# powerbrick_v1.net
KiCad netlist of a schematic drawn in EAGLE
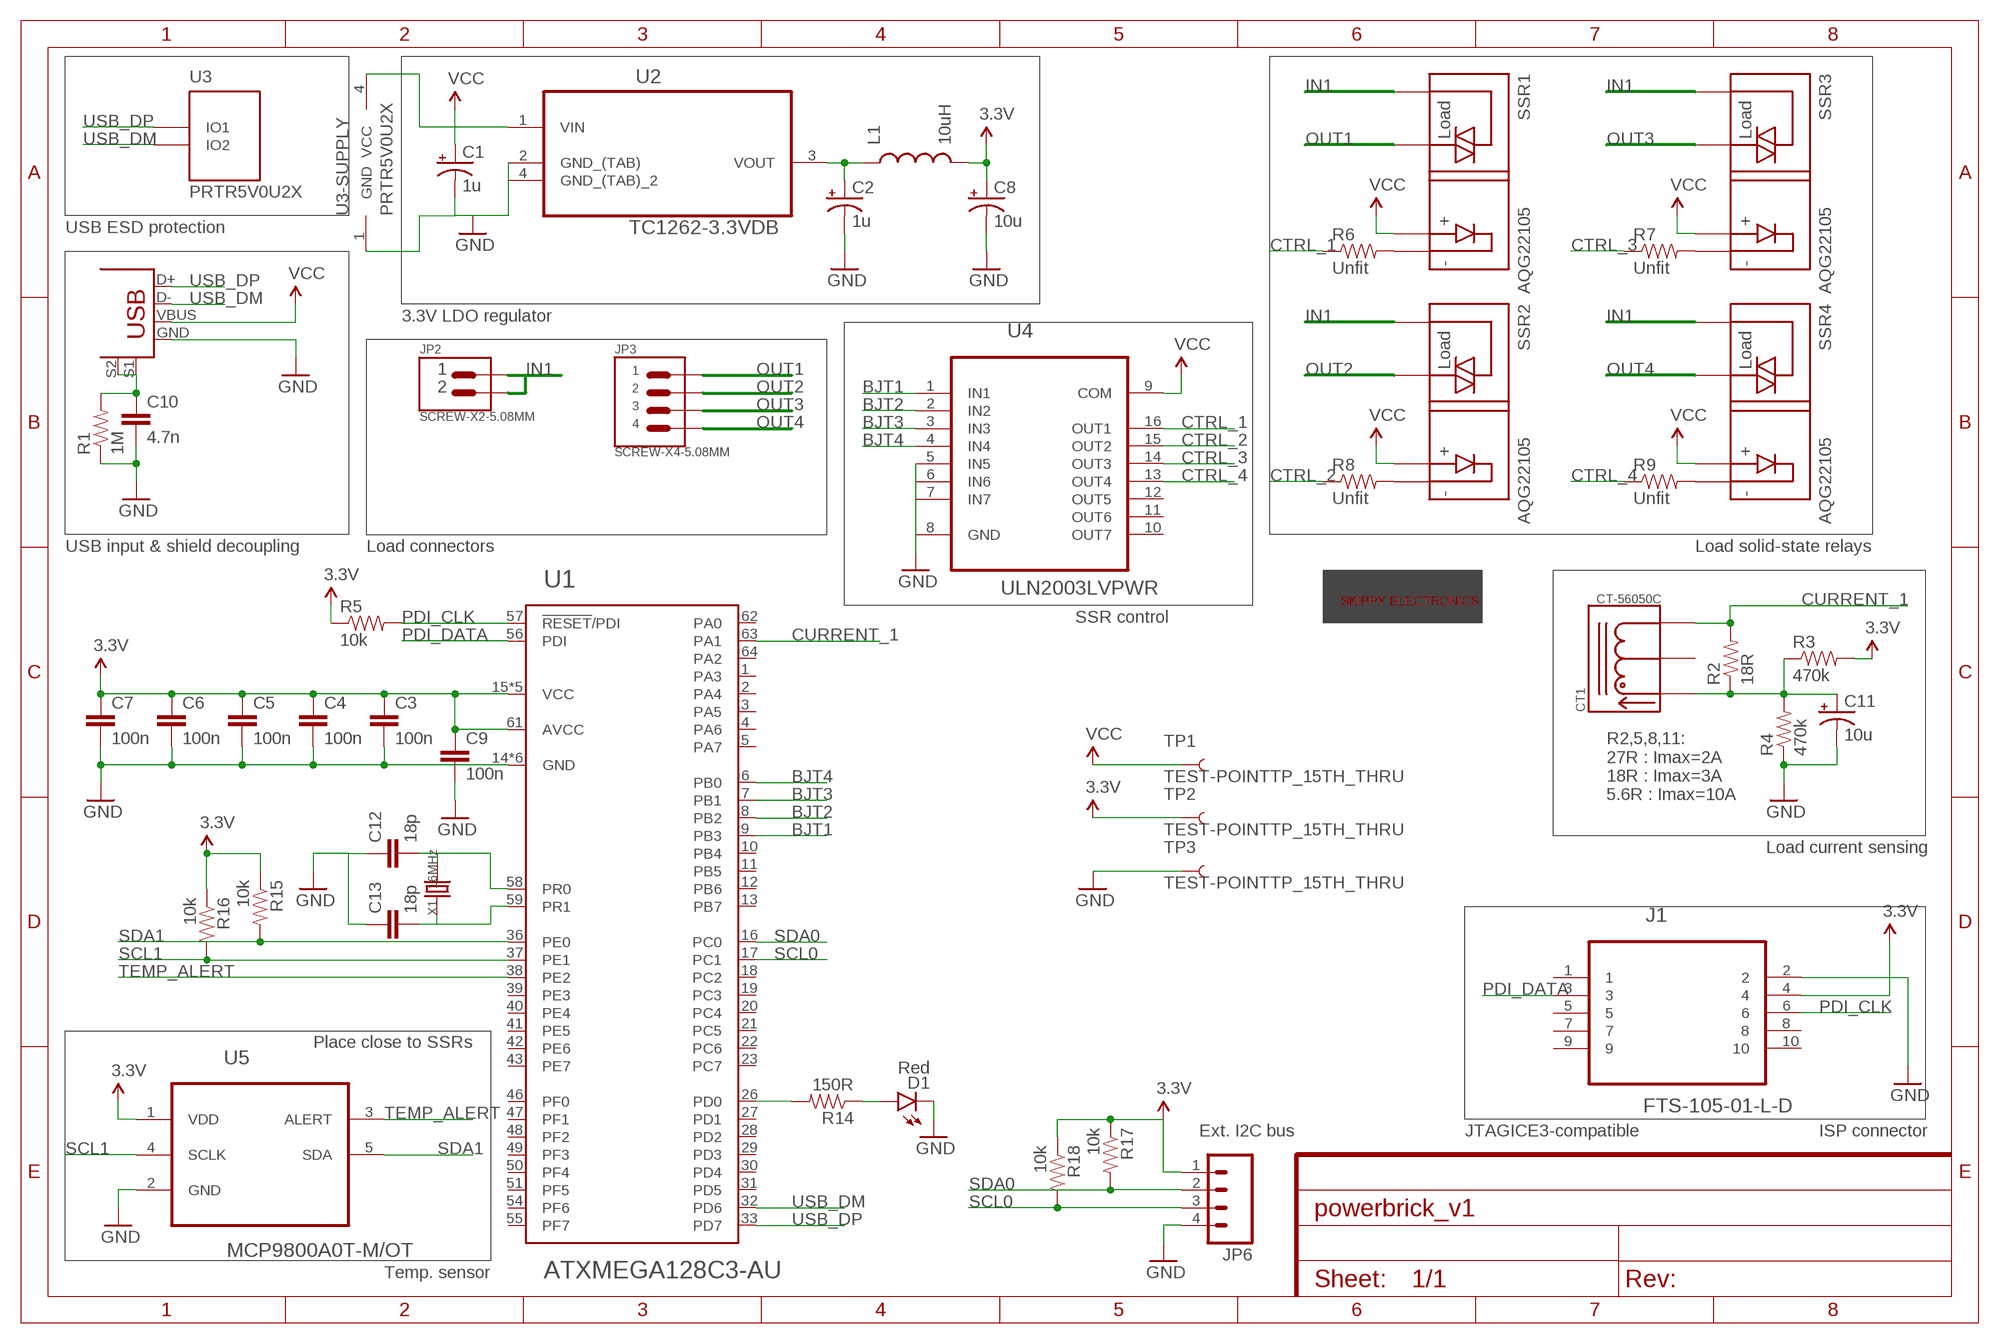
[diagram p0: schematic, sheet 1]

(export (version "E")
  (design (tool "Eeschema 10.0.6"))
  (components
    (comp (ref "C1")
      (value "1u")
      (footprint "eagle-import:EIA3216-KIT")
      (libsource (lib "eagle-import") (part "CAP_POL1206-KIT"))
    )
    (comp (ref "C2")
      (value "1u")
      (footprint "eagle-import:EIA3216-KIT")
      (libsource (lib "eagle-import") (part "CAP_POL1206-KIT"))
    )
    (comp (ref "C3")
      (value "100n")
      (footprint "eagle-import:0805")
      (libsource (lib "eagle-import") (part "CAP0805"))
    )
    (comp (ref "C4")
      (value "100n")
      (footprint "eagle-import:0805")
      (libsource (lib "eagle-import") (part "CAP0805"))
    )
    (comp (ref "C5")
      (value "100n")
      (footprint "eagle-import:0805")
      (libsource (lib "eagle-import") (part "CAP0805"))
    )
    (comp (ref "C6")
      (value "100n")
      (footprint "eagle-import:0805")
      (libsource (lib "eagle-import") (part "CAP0805"))
    )
    (comp (ref "C7")
      (value "100n")
      (footprint "eagle-import:0805")
      (libsource (lib "eagle-import") (part "CAP0805"))
    )
    (comp (ref "C8")
      (value "10u")
      (footprint "eagle-import:EIA3216-KIT")
      (libsource (lib "eagle-import") (part "CAP_POL1206-KIT"))
    )
    (comp (ref "C9")
      (value "100n")
      (footprint "eagle-import:0805")
      (libsource (lib "eagle-import") (part "CAP0805"))
    )
    (comp (ref "C10")
      (value "4.7n")
      (footprint "eagle-import:0805")
      (libsource (lib "eagle-import") (part "CAP0805"))
    )
    (comp (ref "C11")
      (value "10u")
      (footprint "eagle-import:EIA3216-KIT")
      (libsource (lib "eagle-import") (part "CAP_POL1206-KIT"))
    )
    (comp (ref "C12")
      (value "18p")
      (footprint "eagle-import:0805")
      (libsource (lib "eagle-import") (part "CAP0805"))
    )
    (comp (ref "C13")
      (value "18p")
      (footprint "eagle-import:0805")
      (libsource (lib "eagle-import") (part "CAP0805"))
    )
    (comp (ref "CT1")
      (value "CT-56050C")
      (footprint "eagle-import:CT-56050C")
      (libsource (lib "eagle-import") (part "CT-56050C"))
    )
    (comp (ref "D1")
      (value "Red")
      (footprint "eagle-import:LED5MM")
      (libsource (lib "eagle-import") (part "LED5MM"))
    )
    (comp (ref "J1")
      (value "FTS-105-01-L-D")
      (footprint "eagle-import:SAMTEC_FTS-105-01-L-D")
      (libsource (lib "eagle-import") (part "FTS-105-01-L-D"))
    )
    (comp (ref "JP1")
      (value "USB+SHIELD")
      (footprint "eagle-import:USB-B-PTH")
      (libsource (lib "eagle-import") (part "USB+SHIELD"))
    )
    (comp (ref "JP2")
      (value "SCREW-X2-5.08MM")
      (footprint "eagle-import:1X02-5.08MM")
      (libsource (lib "eagle-import") (part "SCREW-X2-5.08MM"))
    )
    (comp (ref "JP3")
      (value "SCREW-X4-5.08MM")
      (footprint "eagle-import:1X04")
      (libsource (lib "eagle-import") (part "SCREW-X4-5.08MM"))
    )
    (comp (ref "JP6")
      (value "M04POLAR_LOCK")
      (footprint "eagle-import:MOLEX-1X4_LOCK")
      (libsource (lib "eagle-import") (part "M04POLAR_LOCK"))
    )
    (comp (ref "L1")
      (value "10uH")
      (footprint "eagle-import:SRN6045")
      (libsource (lib "eagle-import") (part "INDUCTORBOURNS_SRN6045"))
    )
    (comp (ref "R1")
      (value "1M")
      (footprint "eagle-import:0805")
      (libsource (lib "eagle-import") (part "RESISTOR0805-RES"))
    )
    (comp (ref "R2")
      (value "18R")
      (footprint "eagle-import:R2512")
      (libsource (lib "eagle-import") (part "RESISTOR2512"))
    )
    (comp (ref "R3")
      (value "470k")
      (footprint "eagle-import:0805")
      (libsource (lib "eagle-import") (part "RESISTOR0805-RES"))
    )
    (comp (ref "R4")
      (value "470k")
      (footprint "eagle-import:0805")
      (libsource (lib "eagle-import") (part "RESISTOR0805-RES"))
    )
    (comp (ref "R5")
      (value "10k")
      (footprint "eagle-import:0805")
      (libsource (lib "eagle-import") (part "RESISTOR0805-RES"))
    )
    (comp (ref "R6")
      (value "Unfit")
      (footprint "eagle-import:0805")
      (libsource (lib "eagle-import") (part "RESISTOR0805-RES"))
    )
    (comp (ref "R7")
      (value "Unfit")
      (footprint "eagle-import:0805")
      (libsource (lib "eagle-import") (part "RESISTOR0805-RES"))
    )
    (comp (ref "R8")
      (value "Unfit")
      (footprint "eagle-import:0805")
      (libsource (lib "eagle-import") (part "RESISTOR0805-RES"))
    )
    (comp (ref "R9")
      (value "Unfit")
      (footprint "eagle-import:0805")
      (libsource (lib "eagle-import") (part "RESISTOR0805-RES"))
    )
    (comp (ref "R14")
      (value "150R")
      (footprint "eagle-import:0805")
      (libsource (lib "eagle-import") (part "RESISTOR0805-RES"))
    )
    (comp (ref "R15")
      (value "10k")
      (footprint "eagle-import:0805")
      (libsource (lib "eagle-import") (part "RESISTOR0805-RES"))
    )
    (comp (ref "R16")
      (value "10k")
      (footprint "eagle-import:0805")
      (libsource (lib "eagle-import") (part "RESISTOR0805-RES"))
    )
    (comp (ref "R17")
      (value "10k")
      (footprint "eagle-import:0805")
      (libsource (lib "eagle-import") (part "RESISTOR0805-RES"))
    )
    (comp (ref "R18")
      (value "10k")
      (footprint "eagle-import:0805")
      (libsource (lib "eagle-import") (part "RESISTOR0805-RES"))
    )
    (comp (ref "SSR1")
      (value "AQG22105")
      (footprint "eagle-import:SSR-100-400-300")
      (libsource (lib "eagle-import") (part "AQG22105"))
    )
    (comp (ref "SSR2")
      (value "AQG22105")
      (footprint "eagle-import:SSR-100-400-300")
      (libsource (lib "eagle-import") (part "AQG22105"))
    )
    (comp (ref "SSR3")
      (value "AQG22105")
      (footprint "eagle-import:SSR-100-400-300")
      (libsource (lib "eagle-import") (part "AQG22105"))
    )
    (comp (ref "SSR4")
      (value "AQG22105")
      (footprint "eagle-import:SSR-100-400-300")
      (libsource (lib "eagle-import") (part "AQG22105"))
    )
    (comp (ref "TP1")
      (value "TEST-POINTTP_15TH_THRU")
      (footprint "eagle-import:TP_15TH")
      (libsource (lib "eagle-import") (part "TEST-POINTTP_15TH_THRU"))
    )
    (comp (ref "TP2")
      (value "TEST-POINTTP_15TH_THRU")
      (footprint "eagle-import:TP_15TH")
      (libsource (lib "eagle-import") (part "TEST-POINTTP_15TH_THRU"))
    )
    (comp (ref "TP3")
      (value "TEST-POINTTP_15TH_THRU")
      (footprint "eagle-import:TP_15TH")
      (libsource (lib "eagle-import") (part "TEST-POINTTP_15TH_THRU"))
    )
    (comp (ref "U$2")
      (value "SKIPPYTXT-PLC-10MM")
      (footprint "eagle-import:SKIPPYTXT-PLC-10MM")
      (libsource (lib "eagle-import") (part "SKIPPYTXT-PLC-10MM"))
    )
    (comp (ref "U1")
      (value "ATXMEGA128C3-AU")
      (footprint "eagle-import:TQFP-64A-64")
      (libsource (lib "eagle-import") (part "ATXMEGA128C3-AU"))
    )
    (comp (ref "U2")
      (value "TC1262-3.3VDB")
      (footprint "eagle-import:SOT230P700X180-4N")
      (libsource (lib "eagle-import") (part "TC1262-3.3VDB"))
    )
    (comp (ref "U3")
      (value "PRTR5V0U2X")
      (footprint "eagle-import:SOT-143B")
      (libsource (lib "eagle-import") (part "PRTR5V0U2X?"))
    )
    (comp (ref "U4")
      (value "ULN2003LVPWR")
      (footprint "eagle-import:SOP65P640X120-16N")
      (libsource (lib "eagle-import") (part "ULN2003LVPWR"))
    )
    (comp (ref "U5")
      (value "MCP9800A0T-M/OT")
      (footprint "eagle-import:SOT95P280X145-5N")
      (libsource (lib "eagle-import") (part "MCP9800A0T-M/OT"))
    )
    (comp (ref "X1")
      (value "16MHz")
      (footprint "eagle-import:HC49S")
      (libsource (lib "eagle-import") (part "CRYSTAL'HC49S'"))
    )
  )
  (nets
    (net (code "1") (name "/BJT1") (class "Default")
      (node (ref "U1") (pin "9") (pinfunction "PB3_9") (pintype "bidirectional"))
      (node (ref "U4") (pin "1") (pinfunction "IN1_1") (pintype "input"))
    )
    (net (code "2") (name "/BJT2") (class "Default")
      (node (ref "U1") (pin "8") (pinfunction "PB2_8") (pintype "bidirectional"))
      (node (ref "U4") (pin "2") (pinfunction "IN2_2") (pintype "input"))
    )
    (net (code "3") (name "/BJT3") (class "Default")
      (node (ref "U1") (pin "7") (pinfunction "PB1_7") (pintype "bidirectional"))
      (node (ref "U4") (pin "3") (pinfunction "IN3_3") (pintype "input"))
    )
    (net (code "4") (name "/BJT4") (class "Default")
      (node (ref "U1") (pin "6") (pinfunction "PB0_6") (pintype "bidirectional"))
      (node (ref "U4") (pin "4") (pinfunction "IN4_4") (pintype "input"))
    )
    (net (code "5") (name "/CTRL_1") (class "Default")
      (node (ref "R6") (pin "1") (pinfunction "1_1") (pintype "passive"))
      (node (ref "U4") (pin "16") (pinfunction "OUT1_16") (pintype "output"))
    )
    (net (code "6") (name "/CTRL_2") (class "Default")
      (node (ref "R8") (pin "1") (pinfunction "1_1") (pintype "passive"))
      (node (ref "U4") (pin "15") (pinfunction "OUT2_15") (pintype "output"))
    )
    (net (code "7") (name "/CTRL_3") (class "Default")
      (node (ref "R7") (pin "1") (pinfunction "1_1") (pintype "passive"))
      (node (ref "U4") (pin "14") (pinfunction "OUT3_14") (pintype "output"))
    )
    (net (code "8") (name "/CTRL_4") (class "Default")
      (node (ref "R9") (pin "1") (pinfunction "1_1") (pintype "passive"))
      (node (ref "U4") (pin "13") (pinfunction "OUT4_13") (pintype "output"))
    )
    (net (code "9") (name "/CURRENT_1") (class "Default")
      (node (ref "CT1") (pin "P$3") (pinfunction "P$3_P$3") (pintype "bidirectional"))
      (node (ref "R2") (pin "2") (pinfunction "2_2") (pintype "passive"))
      (node (ref "U1") (pin "63") (pinfunction "PA1_63") (pintype "bidirectional"))
    )
    (net (code "10") (name "/IN1") (class "Default")
      (node (ref "JP2") (pin "P$1") (pinfunction "P$1_P$1") (pintype "bidirectional"))
      (node (ref "JP2") (pin "P$2") (pinfunction "P$2_P$2") (pintype "bidirectional"))
      (node (ref "SSR1") (pin "P$4") (pinfunction "P$1_P$4") (pintype "bidirectional"))
      (node (ref "SSR2") (pin "P$4") (pinfunction "P$1_P$4") (pintype "bidirectional"))
      (node (ref "SSR3") (pin "P$4") (pinfunction "P$1_P$4") (pintype "bidirectional"))
      (node (ref "SSR4") (pin "P$4") (pinfunction "P$1_P$4") (pintype "bidirectional"))
    )
    (net (code "11") (name "/OUT1") (class "Default")
      (node (ref "JP3") (pin "P$1") (pinfunction "P$1_P$1") (pintype "bidirectional"))
      (node (ref "SSR1") (pin "P$3") (pinfunction "P$2_P$3") (pintype "bidirectional"))
    )
    (net (code "12") (name "/OUT2") (class "Default")
      (node (ref "JP3") (pin "P$2") (pinfunction "P$2_P$2") (pintype "bidirectional"))
      (node (ref "SSR2") (pin "P$3") (pinfunction "P$2_P$3") (pintype "bidirectional"))
    )
    (net (code "13") (name "/OUT3") (class "Default")
      (node (ref "JP3") (pin "P$3") (pinfunction "P$3_P$3") (pintype "bidirectional"))
      (node (ref "SSR3") (pin "P$3") (pinfunction "P$2_P$3") (pintype "bidirectional"))
    )
    (net (code "14") (name "/OUT4") (class "Default")
      (node (ref "JP3") (pin "P$4") (pinfunction "P$4_P$4") (pintype "bidirectional"))
      (node (ref "SSR4") (pin "P$3") (pinfunction "P$2_P$3") (pintype "bidirectional"))
    )
    (net (code "15") (name "/PDI_CLK") (class "Default")
      (node (ref "J1") (pin "6") (pinfunction "6_6") (pintype "passive"))
      (node (ref "R5") (pin "2") (pinfunction "2_2") (pintype "passive"))
      (node (ref "U1") (pin "57") (pinfunction "~{RESET}/PDI_57") (pintype "bidirectional"))
    )
    (net (code "16") (name "/PDI_DATA") (class "Default")
      (node (ref "J1") (pin "3") (pinfunction "3_3") (pintype "passive"))
      (node (ref "U1") (pin "56") (pinfunction "PDI_56") (pintype "bidirectional"))
    )
    (net (code "17") (name "/SCL0") (class "Default")
      (node (ref "JP6") (pin "3") (pinfunction "3_3") (pintype "passive"))
      (node (ref "R18") (pin "2") (pinfunction "2_2") (pintype "passive"))
      (node (ref "U1") (pin "17") (pinfunction "PC1_17") (pintype "bidirectional"))
    )
    (net (code "18") (name "/SCL1") (class "Default")
      (node (ref "R16") (pin "2") (pinfunction "2_2") (pintype "passive"))
      (node (ref "U1") (pin "37") (pinfunction "PE1_37") (pintype "bidirectional"))
      (node (ref "U5") (pin "4") (pinfunction "SCLK_4") (pintype "input"))
    )
    (net (code "19") (name "/SDA0") (class "Default")
      (node (ref "JP6") (pin "2") (pinfunction "2_2") (pintype "passive"))
      (node (ref "R17") (pin "2") (pinfunction "2_2") (pintype "passive"))
      (node (ref "U1") (pin "16") (pinfunction "PC0_16") (pintype "bidirectional"))
    )
    (net (code "20") (name "/SDA1") (class "Default")
      (node (ref "R15") (pin "2") (pinfunction "2_2") (pintype "passive"))
      (node (ref "U1") (pin "36") (pinfunction "PE0_36") (pintype "bidirectional"))
      (node (ref "U5") (pin "5") (pinfunction "SDA_5") (pintype "bidirectional"))
    )
    (net (code "21") (name "/TEMP_ALERT") (class "Default")
      (node (ref "U1") (pin "38") (pinfunction "PE2_38") (pintype "bidirectional"))
      (node (ref "U5") (pin "3") (pinfunction "ALERT_3") (pintype "output"))
    )
    (net (code "22") (name "/USB_DM") (class "Default")
      (node (ref "JP1") (pin "D-") (pinfunction "D-_D-") (pintype "bidirectional"))
      (node (ref "U1") (pin "32") (pinfunction "PD6_32") (pintype "bidirectional"))
      (node (ref "U3") (pin "3") (pinfunction "IO2_3") (pintype "bidirectional"))
    )
    (net (code "23") (name "/USB_DP") (class "Default")
      (node (ref "JP1") (pin "D+") (pinfunction "D+_D+") (pintype "bidirectional"))
      (node (ref "U1") (pin "33") (pinfunction "PD7_33") (pintype "bidirectional"))
      (node (ref "U3") (pin "2") (pinfunction "IO1_2") (pintype "bidirectional"))
    )
    (net (code "24") (name "3.3V") (class "Default")
      (node (ref "C3") (pin "1") (pinfunction "1_1") (pintype "passive"))
      (node (ref "C4") (pin "1") (pinfunction "1_1") (pintype "passive"))
      (node (ref "C5") (pin "1") (pinfunction "1_1") (pintype "passive"))
      (node (ref "C6") (pin "1") (pinfunction "1_1") (pintype "passive"))
      (node (ref "C7") (pin "1") (pinfunction "1_1") (pintype "passive"))
      (node (ref "C8") (pin "A") (pinfunction "+_A") (pintype "passive"))
      (node (ref "C9") (pin "1") (pinfunction "1_1") (pintype "passive"))
      (node (ref "J1") (pin "4") (pinfunction "4_4") (pintype "passive"))
      (node (ref "JP6") (pin "1") (pinfunction "1_1") (pintype "passive"))
      (node (ref "L1") (pin "2") (pinfunction "2_2") (pintype "passive"))
      (node (ref "R15") (pin "1") (pinfunction "1_1") (pintype "passive"))
      (node (ref "R16") (pin "1") (pinfunction "1_1") (pintype "passive"))
      (node (ref "R17") (pin "1") (pinfunction "1_1") (pintype "passive"))
      (node (ref "R18") (pin "1") (pinfunction "1_1") (pintype "passive"))
      (node (ref "R3") (pin "2") (pinfunction "2_2") (pintype "passive"))
      (node (ref "R5") (pin "1") (pinfunction "1_1") (pintype "passive"))
      (node (ref "TP2") (pin "P$1") (pinfunction "1_P$1") (pintype "bidirectional"))
      (node (ref "U1") (pin "15") (pinfunction "VCC_15") (pintype "power_in"))
      (node (ref "U1") (pin "25") (pinfunction "VCC_25") (pintype "power_in"))
      (node (ref "U1") (pin "35") (pinfunction "VCC_35") (pintype "power_in"))
      (node (ref "U1") (pin "45") (pinfunction "VCC_45") (pintype "power_in"))
      (node (ref "U1") (pin "53") (pinfunction "VCC_53") (pintype "power_in"))
      (node (ref "U1") (pin "61") (pinfunction "AVCC_61") (pintype "power_in"))
      (node (ref "U5") (pin "1") (pinfunction "VDD_1") (pintype "power_in"))
    )
    (net (code "25") (name "GND") (class "Default")
      (node (ref "C1") (pin "C") (pinfunction "-_C") (pintype "passive"))
      (node (ref "C10") (pin "2") (pinfunction "2_2") (pintype "passive"))
      (node (ref "C11") (pin "C") (pinfunction "-_C") (pintype "passive"))
      (node (ref "C12") (pin "1") (pinfunction "1_1") (pintype "passive"))
      (node (ref "C13") (pin "1") (pinfunction "1_1") (pintype "passive"))
      (node (ref "C2") (pin "C") (pinfunction "-_C") (pintype "passive"))
      (node (ref "C3") (pin "2") (pinfunction "2_2") (pintype "passive"))
      (node (ref "C4") (pin "2") (pinfunction "2_2") (pintype "passive"))
      (node (ref "C5") (pin "2") (pinfunction "2_2") (pintype "passive"))
      (node (ref "C6") (pin "2") (pinfunction "2_2") (pintype "passive"))
      (node (ref "C7") (pin "2") (pinfunction "2_2") (pintype "passive"))
      (node (ref "C8") (pin "C") (pinfunction "-_C") (pintype "passive"))
      (node (ref "C9") (pin "2") (pinfunction "2_2") (pintype "passive"))
      (node (ref "D1") (pin "K") (pinfunction "C_K") (pintype "passive"))
      (node (ref "J1") (pin "2") (pinfunction "2_2") (pintype "passive"))
      (node (ref "JP1") (pin "GND") (pinfunction "GND_GND") (pintype "bidirectional"))
      (node (ref "JP6") (pin "4") (pinfunction "4_4") (pintype "passive"))
      (node (ref "R1") (pin "1") (pinfunction "1_1") (pintype "passive"))
      (node (ref "R4") (pin "1") (pinfunction "1_1") (pintype "passive"))
      (node (ref "TP3") (pin "P$1") (pinfunction "1_P$1") (pintype "bidirectional"))
      (node (ref "U1") (pin "14") (pinfunction "GND_14") (pintype "power_in"))
      (node (ref "U1") (pin "24") (pinfunction "GND_24") (pintype "power_in"))
      (node (ref "U1") (pin "34") (pinfunction "GND_34") (pintype "power_in"))
      (node (ref "U1") (pin "44") (pinfunction "GND_44") (pintype "power_in"))
      (node (ref "U1") (pin "52") (pinfunction "GND_52") (pintype "power_in"))
      (node (ref "U1") (pin "60") (pinfunction "GND_60") (pintype "power_in"))
      (node (ref "U2") (pin "2") (pinfunction "GND_(TAB)_2") (pintype "passive"))
      (node (ref "U2") (pin "4") (pinfunction "GND_(TAB)_2_4") (pintype "passive"))
      (node (ref "U3") (pin "1") (pinfunction "GND_1") (pintype "bidirectional"))
      (node (ref "U4") (pin "5") (pinfunction "IN5_5") (pintype "input"))
      (node (ref "U4") (pin "6") (pinfunction "IN6_6") (pintype "input"))
      (node (ref "U4") (pin "7") (pinfunction "IN7_7") (pintype "input"))
      (node (ref "U4") (pin "8") (pinfunction "GND_8") (pintype "passive"))
      (node (ref "U5") (pin "2") (pinfunction "GND_2") (pintype "passive"))
    )
    (net (code "26") (name "Net-(C2-+)") (class "Default")
      (node (ref "C2") (pin "A") (pinfunction "+_A") (pintype "passive"))
      (node (ref "L1") (pin "1") (pinfunction "1_1") (pintype "passive"))
      (node (ref "U2") (pin "3") (pinfunction "VOUT_3") (pintype "output"))
    )
    (net (code "27") (name "Net-(C10-Pad1)") (class "Default")
      (node (ref "C10") (pin "1") (pinfunction "1_1") (pintype "passive"))
      (node (ref "JP1") (pin "S1") (pinfunction "S1_S1") (pintype "bidirectional"))
      (node (ref "JP1") (pin "S2") (pinfunction "S2_S2") (pintype "bidirectional"))
      (node (ref "R1") (pin "2") (pinfunction "2_2") (pintype "passive"))
    )
    (net (code "28") (name "Net-(C11-+)") (class "Default")
      (node (ref "C11") (pin "A") (pinfunction "+_A") (pintype "passive"))
      (node (ref "CT1") (pin "P$1") (pinfunction "P$1_P$1") (pintype "bidirectional"))
      (node (ref "R2") (pin "1") (pinfunction "1_1") (pintype "passive"))
      (node (ref "R3") (pin "1") (pinfunction "1_1") (pintype "passive"))
      (node (ref "R4") (pin "2") (pinfunction "2_2") (pintype "passive"))
    )
    (net (code "29") (name "Net-(D1-PadA)") (class "Default")
      (node (ref "D1") (pin "A") (pinfunction "A_A") (pintype "passive"))
      (node (ref "R14") (pin "1") (pinfunction "1_1") (pintype "passive"))
    )
    (net (code "30") (name "Net-(SSR1-P$4)") (class "Default")
      (node (ref "R6") (pin "2") (pinfunction "2_2") (pintype "passive"))
      (node (ref "SSR1") (pin "P$1") (pinfunction "P$4_P$1") (pintype "output"))
    )
    (net (code "31") (name "Net-(SSR2-P$4)") (class "Default")
      (node (ref "R8") (pin "2") (pinfunction "2_2") (pintype "passive"))
      (node (ref "SSR2") (pin "P$1") (pinfunction "P$4_P$1") (pintype "output"))
    )
    (net (code "32") (name "Net-(SSR3-P$4)") (class "Default")
      (node (ref "R7") (pin "2") (pinfunction "2_2") (pintype "passive"))
      (node (ref "SSR3") (pin "P$1") (pinfunction "P$4_P$1") (pintype "output"))
    )
    (net (code "33") (name "Net-(SSR4-P$4)") (class "Default")
      (node (ref "R9") (pin "2") (pinfunction "2_2") (pintype "passive"))
      (node (ref "SSR4") (pin "P$1") (pinfunction "P$4_P$1") (pintype "output"))
    )
    (net (code "34") (name "Net-(U1-PD0)") (class "Default")
      (node (ref "R14") (pin "2") (pinfunction "2_2") (pintype "passive"))
      (node (ref "U1") (pin "26") (pinfunction "PD0_26") (pintype "bidirectional"))
    )
    (net (code "35") (name "Net-(U1-PR0)") (class "Default")
      (node (ref "C12") (pin "2") (pinfunction "2_2") (pintype "passive"))
      (node (ref "U1") (pin "58") (pinfunction "PR0_58") (pintype "bidirectional"))
      (node (ref "X1") (pin "2") (pinfunction "2_2") (pintype "passive"))
    )
    (net (code "36") (name "Net-(U1-PR1)") (class "Default")
      (node (ref "C13") (pin "2") (pinfunction "2_2") (pintype "passive"))
      (node (ref "U1") (pin "59") (pinfunction "PR1_59") (pintype "bidirectional"))
      (node (ref "X1") (pin "1") (pinfunction "1_1") (pintype "passive"))
    )
    (net (code "37") (name "VCC") (class "Default")
      (node (ref "C1") (pin "A") (pinfunction "+_A") (pintype "passive"))
      (node (ref "JP1") (pin "VBUS") (pinfunction "VBUS_VBUS") (pintype "bidirectional"))
      (node (ref "SSR1") (pin "P$2") (pinfunction "P$3_P$2") (pintype "input"))
      (node (ref "SSR2") (pin "P$2") (pinfunction "P$3_P$2") (pintype "input"))
      (node (ref "SSR3") (pin "P$2") (pinfunction "P$3_P$2") (pintype "input"))
      (node (ref "SSR4") (pin "P$2") (pinfunction "P$3_P$2") (pintype "input"))
      (node (ref "TP1") (pin "P$1") (pinfunction "1_P$1") (pintype "bidirectional"))
      (node (ref "U2") (pin "1") (pinfunction "VIN_1") (pintype "input"))
      (node (ref "U3") (pin "4") (pinfunction "VCC_4") (pintype "bidirectional"))
      (node (ref "U4") (pin "9") (pinfunction "COM_9") (pintype "output"))
    )
    (net (code "38") (name "unconnected-(CT1-PadP$2)") (class "Default")
      (node (ref "CT1") (pin "P$2") (pinfunction "P$2_P$2") (pintype "bidirectional"))
    )
    (net (code "39") (name "unconnected-(J1-Pad1)") (class "Default")
      (node (ref "J1") (pin "1") (pinfunction "1_1") (pintype "passive"))
    )
    (net (code "40") (name "unconnected-(J1-Pad5)") (class "Default")
      (node (ref "J1") (pin "5") (pinfunction "5_5") (pintype "passive"))
    )
    (net (code "41") (name "unconnected-(J1-Pad7)") (class "Default")
      (node (ref "J1") (pin "7") (pinfunction "7_7") (pintype "passive"))
    )
    (net (code "42") (name "unconnected-(J1-Pad8)") (class "Default")
      (node (ref "J1") (pin "8") (pinfunction "8_8") (pintype "passive"))
    )
    (net (code "43") (name "unconnected-(J1-Pad9)") (class "Default")
      (node (ref "J1") (pin "9") (pinfunction "9_9") (pintype "passive"))
    )
    (net (code "44") (name "unconnected-(J1-Pad10)") (class "Default")
      (node (ref "J1") (pin "10") (pinfunction "10_10") (pintype "passive"))
    )
    (net (code "45") (name "unconnected-(U1-PA0-Pad62)") (class "Default")
      (node (ref "U1") (pin "62") (pinfunction "PA0_62") (pintype "bidirectional"))
    )
    (net (code "46") (name "unconnected-(U1-PA2-Pad64)") (class "Default")
      (node (ref "U1") (pin "64") (pinfunction "PA2_64") (pintype "bidirectional"))
    )
    (net (code "47") (name "unconnected-(U1-PA3-Pad1)") (class "Default")
      (node (ref "U1") (pin "1") (pinfunction "PA3_1") (pintype "bidirectional"))
    )
    (net (code "48") (name "unconnected-(U1-PA4-Pad2)") (class "Default")
      (node (ref "U1") (pin "2") (pinfunction "PA4_2") (pintype "bidirectional"))
    )
    (net (code "49") (name "unconnected-(U1-PA5-Pad3)") (class "Default")
      (node (ref "U1") (pin "3") (pinfunction "PA5_3") (pintype "bidirectional"))
    )
    (net (code "50") (name "unconnected-(U1-PA6-Pad4)") (class "Default")
      (node (ref "U1") (pin "4") (pinfunction "PA6_4") (pintype "bidirectional"))
    )
    (net (code "51") (name "unconnected-(U1-PA7-Pad5)") (class "Default")
      (node (ref "U1") (pin "5") (pinfunction "PA7_5") (pintype "bidirectional"))
    )
    (net (code "52") (name "unconnected-(U1-PB4-Pad10)") (class "Default")
      (node (ref "U1") (pin "10") (pinfunction "PB4_10") (pintype "bidirectional"))
    )
    (net (code "53") (name "unconnected-(U1-PB5-Pad11)") (class "Default")
      (node (ref "U1") (pin "11") (pinfunction "PB5_11") (pintype "bidirectional"))
    )
    (net (code "54") (name "unconnected-(U1-PB6-Pad12)") (class "Default")
      (node (ref "U1") (pin "12") (pinfunction "PB6_12") (pintype "bidirectional"))
    )
    (net (code "55") (name "unconnected-(U1-PB7-Pad13)") (class "Default")
      (node (ref "U1") (pin "13") (pinfunction "PB7_13") (pintype "bidirectional"))
    )
    (net (code "56") (name "unconnected-(U1-PC2-Pad18)") (class "Default")
      (node (ref "U1") (pin "18") (pinfunction "PC2_18") (pintype "bidirectional"))
    )
    (net (code "57") (name "unconnected-(U1-PC3-Pad19)") (class "Default")
      (node (ref "U1") (pin "19") (pinfunction "PC3_19") (pintype "bidirectional"))
    )
    (net (code "58") (name "unconnected-(U1-PC4-Pad20)") (class "Default")
      (node (ref "U1") (pin "20") (pinfunction "PC4_20") (pintype "bidirectional"))
    )
    (net (code "59") (name "unconnected-(U1-PC5-Pad21)") (class "Default")
      (node (ref "U1") (pin "21") (pinfunction "PC5_21") (pintype "bidirectional"))
    )
    (net (code "60") (name "unconnected-(U1-PC6-Pad22)") (class "Default")
      (node (ref "U1") (pin "22") (pinfunction "PC6_22") (pintype "bidirectional"))
    )
    (net (code "61") (name "unconnected-(U1-PC7-Pad23)") (class "Default")
      (node (ref "U1") (pin "23") (pinfunction "PC7_23") (pintype "bidirectional"))
    )
    (net (code "62") (name "unconnected-(U1-PD1-Pad27)") (class "Default")
      (node (ref "U1") (pin "27") (pinfunction "PD1_27") (pintype "bidirectional"))
    )
    (net (code "63") (name "unconnected-(U1-PD2-Pad28)") (class "Default")
      (node (ref "U1") (pin "28") (pinfunction "PD2_28") (pintype "bidirectional"))
    )
    (net (code "64") (name "unconnected-(U1-PD3-Pad29)") (class "Default")
      (node (ref "U1") (pin "29") (pinfunction "PD3_29") (pintype "bidirectional"))
    )
    (net (code "65") (name "unconnected-(U1-PD4-Pad30)") (class "Default")
      (node (ref "U1") (pin "30") (pinfunction "PD4_30") (pintype "bidirectional"))
    )
    (net (code "66") (name "unconnected-(U1-PD5-Pad31)") (class "Default")
      (node (ref "U1") (pin "31") (pinfunction "PD5_31") (pintype "bidirectional"))
    )
    (net (code "67") (name "unconnected-(U1-PE3-Pad39)") (class "Default")
      (node (ref "U1") (pin "39") (pinfunction "PE3_39") (pintype "bidirectional"))
    )
    (net (code "68") (name "unconnected-(U1-PE4-Pad40)") (class "Default")
      (node (ref "U1") (pin "40") (pinfunction "PE4_40") (pintype "bidirectional"))
    )
    (net (code "69") (name "unconnected-(U1-PE5-Pad41)") (class "Default")
      (node (ref "U1") (pin "41") (pinfunction "PE5_41") (pintype "bidirectional"))
    )
    (net (code "70") (name "unconnected-(U1-PE6-Pad42)") (class "Default")
      (node (ref "U1") (pin "42") (pinfunction "PE6_42") (pintype "bidirectional"))
    )
    (net (code "71") (name "unconnected-(U1-PE7-Pad43)") (class "Default")
      (node (ref "U1") (pin "43") (pinfunction "PE7_43") (pintype "bidirectional"))
    )
    (net (code "72") (name "unconnected-(U1-PF0-Pad46)") (class "Default")
      (node (ref "U1") (pin "46") (pinfunction "PF0_46") (pintype "bidirectional"))
    )
    (net (code "73") (name "unconnected-(U1-PF1-Pad47)") (class "Default")
      (node (ref "U1") (pin "47") (pinfunction "PF1_47") (pintype "bidirectional"))
    )
    (net (code "74") (name "unconnected-(U1-PF2-Pad48)") (class "Default")
      (node (ref "U1") (pin "48") (pinfunction "PF2_48") (pintype "bidirectional"))
    )
    (net (code "75") (name "unconnected-(U1-PF3-Pad49)") (class "Default")
      (node (ref "U1") (pin "49") (pinfunction "PF3_49") (pintype "bidirectional"))
    )
    (net (code "76") (name "unconnected-(U1-PF4-Pad50)") (class "Default")
      (node (ref "U1") (pin "50") (pinfunction "PF4_50") (pintype "bidirectional"))
    )
    (net (code "77") (name "unconnected-(U1-PF5-Pad51)") (class "Default")
      (node (ref "U1") (pin "51") (pinfunction "PF5_51") (pintype "bidirectional"))
    )
    (net (code "78") (name "unconnected-(U1-PF6-Pad54)") (class "Default")
      (node (ref "U1") (pin "54") (pinfunction "PF6_54") (pintype "bidirectional"))
    )
    (net (code "79") (name "unconnected-(U1-PF7-Pad55)") (class "Default")
      (node (ref "U1") (pin "55") (pinfunction "PF7_55") (pintype "bidirectional"))
    )
    (net (code "80") (name "unconnected-(U4-OUT5-Pad12)") (class "Default")
      (node (ref "U4") (pin "12") (pinfunction "OUT5_12") (pintype "output"))
    )
    (net (code "81") (name "unconnected-(U4-OUT6-Pad11)") (class "Default")
      (node (ref "U4") (pin "11") (pinfunction "OUT6_11") (pintype "output"))
    )
    (net (code "82") (name "unconnected-(U4-OUT7-Pad10)") (class "Default")
      (node (ref "U4") (pin "10") (pinfunction "OUT7_10") (pintype "output"))
    )
  )
)
